# lightBarV2_a.net
KiCad netlist of a schematic drawn in EAGLE
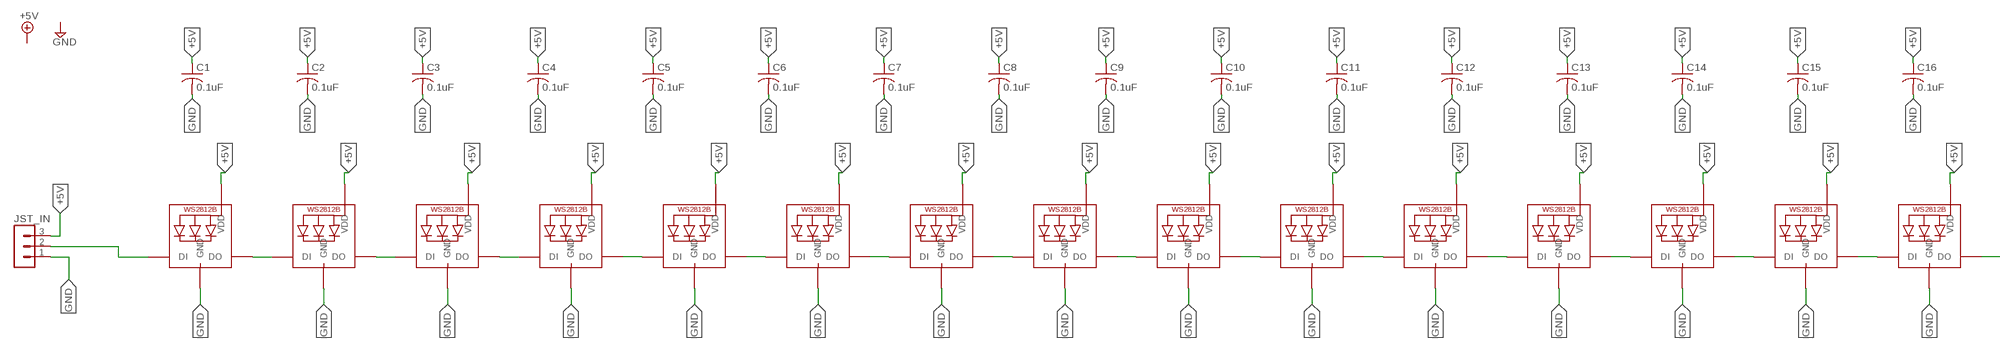
[diagram p0: schematic, sheet 1, part 1 of 2]
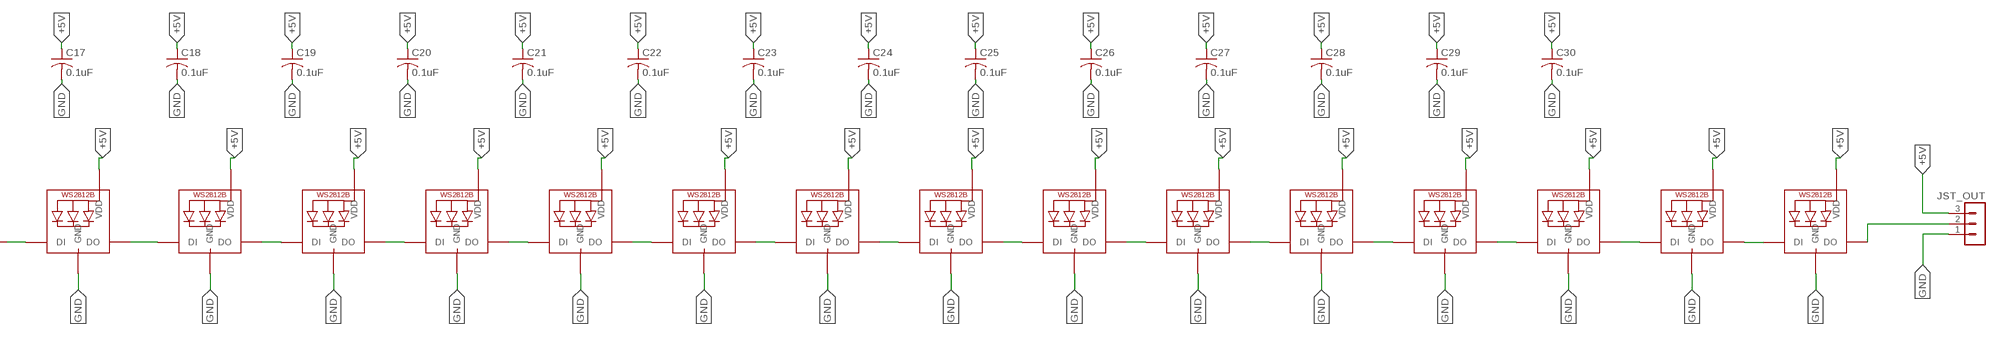
[diagram p1: schematic, sheet 1, part 2 of 2]

(export (version "E")
  (design (tool "Eeschema 10.0.6"))
  (components
    (comp (ref "C1")
      (value "0.1uF")
      (footprint "eagle-import:C0805K")
      (libsource (lib "eagle-import") (part "C-USC0805K"))
    )
    (comp (ref "C2")
      (value "0.1uF")
      (footprint "eagle-import:C0805K")
      (libsource (lib "eagle-import") (part "C-USC0805K"))
    )
    (comp (ref "C3")
      (value "0.1uF")
      (footprint "eagle-import:C0805K")
      (libsource (lib "eagle-import") (part "C-USC0805K"))
    )
    (comp (ref "C4")
      (value "0.1uF")
      (footprint "eagle-import:C0805K")
      (libsource (lib "eagle-import") (part "C-USC0805K"))
    )
    (comp (ref "C5")
      (value "0.1uF")
      (footprint "eagle-import:C0805K")
      (libsource (lib "eagle-import") (part "C-USC0805K"))
    )
    (comp (ref "C6")
      (value "0.1uF")
      (footprint "eagle-import:C0805K")
      (libsource (lib "eagle-import") (part "C-USC0805K"))
    )
    (comp (ref "C7")
      (value "0.1uF")
      (footprint "eagle-import:C0805K")
      (libsource (lib "eagle-import") (part "C-USC0805K"))
    )
    (comp (ref "C8")
      (value "0.1uF")
      (footprint "eagle-import:C0805K")
      (libsource (lib "eagle-import") (part "C-USC0805K"))
    )
    (comp (ref "C9")
      (value "0.1uF")
      (footprint "eagle-import:C0805K")
      (libsource (lib "eagle-import") (part "C-USC0805K"))
    )
    (comp (ref "C10")
      (value "0.1uF")
      (footprint "eagle-import:C0805K")
      (libsource (lib "eagle-import") (part "C-USC0805K"))
    )
    (comp (ref "C11")
      (value "0.1uF")
      (footprint "eagle-import:C0805K")
      (libsource (lib "eagle-import") (part "C-USC0805K"))
    )
    (comp (ref "C12")
      (value "0.1uF")
      (footprint "eagle-import:C0805K")
      (libsource (lib "eagle-import") (part "C-USC0805K"))
    )
    (comp (ref "C13")
      (value "0.1uF")
      (footprint "eagle-import:C0805K")
      (libsource (lib "eagle-import") (part "C-USC0805K"))
    )
    (comp (ref "C14")
      (value "0.1uF")
      (footprint "eagle-import:C0805K")
      (libsource (lib "eagle-import") (part "C-USC0805K"))
    )
    (comp (ref "C15")
      (value "0.1uF")
      (footprint "eagle-import:C0805K")
      (libsource (lib "eagle-import") (part "C-USC0805K"))
    )
    (comp (ref "C16")
      (value "0.1uF")
      (footprint "eagle-import:C0805K")
      (libsource (lib "eagle-import") (part "C-USC0805K"))
    )
    (comp (ref "C17")
      (value "0.1uF")
      (footprint "eagle-import:C0805K")
      (libsource (lib "eagle-import") (part "C-USC0805K"))
    )
    (comp (ref "C18")
      (value "0.1uF")
      (footprint "eagle-import:C0805K")
      (libsource (lib "eagle-import") (part "C-USC0805K"))
    )
    (comp (ref "C19")
      (value "0.1uF")
      (footprint "eagle-import:C0805K")
      (libsource (lib "eagle-import") (part "C-USC0805K"))
    )
    (comp (ref "C20")
      (value "0.1uF")
      (footprint "eagle-import:C0805K")
      (libsource (lib "eagle-import") (part "C-USC0805K"))
    )
    (comp (ref "C21")
      (value "0.1uF")
      (footprint "eagle-import:C0805K")
      (libsource (lib "eagle-import") (part "C-USC0805K"))
    )
    (comp (ref "C22")
      (value "0.1uF")
      (footprint "eagle-import:C0805K")
      (libsource (lib "eagle-import") (part "C-USC0805K"))
    )
    (comp (ref "C23")
      (value "0.1uF")
      (footprint "eagle-import:C0805K")
      (libsource (lib "eagle-import") (part "C-USC0805K"))
    )
    (comp (ref "C24")
      (value "0.1uF")
      (footprint "eagle-import:C0805K")
      (libsource (lib "eagle-import") (part "C-USC0805K"))
    )
    (comp (ref "C25")
      (value "0.1uF")
      (footprint "eagle-import:C0805K")
      (libsource (lib "eagle-import") (part "C-USC0805K"))
    )
    (comp (ref "C26")
      (value "0.1uF")
      (footprint "eagle-import:C0805K")
      (libsource (lib "eagle-import") (part "C-USC0805K"))
    )
    (comp (ref "C27")
      (value "0.1uF")
      (footprint "eagle-import:C0805K")
      (libsource (lib "eagle-import") (part "C-USC0805K"))
    )
    (comp (ref "C28")
      (value "0.1uF")
      (footprint "eagle-import:C0805K")
      (libsource (lib "eagle-import") (part "C-USC0805K"))
    )
    (comp (ref "C29")
      (value "0.1uF")
      (footprint "eagle-import:C0805K")
      (libsource (lib "eagle-import") (part "C-USC0805K"))
    )
    (comp (ref "C30")
      (value "0.1uF")
      (footprint "eagle-import:C0805K")
      (libsource (lib "eagle-import") (part "C-USC0805K"))
    )
    (comp (ref "JST_IN")
      (value "B3B-XH-2")
      (footprint "eagle-import:B3B-XH-A")
      (libsource (lib "eagle-import") (part "B3B-XH-2"))
    )
    (comp (ref "JST_OUT")
      (value "B3B-XH-2")
      (footprint "eagle-import:B3B-XH-A")
      (libsource (lib "eagle-import") (part "B3B-XH-2"))
    )
    (comp (ref "LED1")
      (value "WS2812B5050")
      (footprint "eagle-import:WS2812B")
      (libsource (lib "eagle-import") (part "WS2812B5050"))
    )
    (comp (ref "LED2")
      (value "WS2812B5050")
      (footprint "eagle-import:WS2812B")
      (libsource (lib "eagle-import") (part "WS2812B5050"))
    )
    (comp (ref "LED3")
      (value "WS2812B5050")
      (footprint "eagle-import:WS2812B")
      (libsource (lib "eagle-import") (part "WS2812B5050"))
    )
    (comp (ref "LED4")
      (value "WS2812B5050")
      (footprint "eagle-import:WS2812B")
      (libsource (lib "eagle-import") (part "WS2812B5050"))
    )
    (comp (ref "LED5")
      (value "WS2812B5050")
      (footprint "eagle-import:WS2812B")
      (libsource (lib "eagle-import") (part "WS2812B5050"))
    )
    (comp (ref "LED6")
      (value "WS2812B5050")
      (footprint "eagle-import:WS2812B")
      (libsource (lib "eagle-import") (part "WS2812B5050"))
    )
    (comp (ref "LED7")
      (value "WS2812B5050")
      (footprint "eagle-import:WS2812B")
      (libsource (lib "eagle-import") (part "WS2812B5050"))
    )
    (comp (ref "LED8")
      (value "WS2812B5050")
      (footprint "eagle-import:WS2812B")
      (libsource (lib "eagle-import") (part "WS2812B5050"))
    )
    (comp (ref "LED9")
      (value "WS2812B5050")
      (footprint "eagle-import:WS2812B")
      (libsource (lib "eagle-import") (part "WS2812B5050"))
    )
    (comp (ref "LED10")
      (value "WS2812B5050")
      (footprint "eagle-import:WS2812B")
      (libsource (lib "eagle-import") (part "WS2812B5050"))
    )
    (comp (ref "LED11")
      (value "WS2812B5050")
      (footprint "eagle-import:WS2812B")
      (libsource (lib "eagle-import") (part "WS2812B5050"))
    )
    (comp (ref "LED12")
      (value "WS2812B5050")
      (footprint "eagle-import:WS2812B")
      (libsource (lib "eagle-import") (part "WS2812B5050"))
    )
    (comp (ref "LED13")
      (value "WS2812B5050")
      (footprint "eagle-import:WS2812B")
      (libsource (lib "eagle-import") (part "WS2812B5050"))
    )
    (comp (ref "LED14")
      (value "WS2812B5050")
      (footprint "eagle-import:WS2812B")
      (libsource (lib "eagle-import") (part "WS2812B5050"))
    )
    (comp (ref "LED15")
      (value "WS2812B5050")
      (footprint "eagle-import:WS2812B")
      (libsource (lib "eagle-import") (part "WS2812B5050"))
    )
    (comp (ref "LED16")
      (value "WS2812B5050")
      (footprint "eagle-import:WS2812B")
      (libsource (lib "eagle-import") (part "WS2812B5050"))
    )
    (comp (ref "LED17")
      (value "WS2812B5050")
      (footprint "eagle-import:WS2812B")
      (libsource (lib "eagle-import") (part "WS2812B5050"))
    )
    (comp (ref "LED18")
      (value "WS2812B5050")
      (footprint "eagle-import:WS2812B")
      (libsource (lib "eagle-import") (part "WS2812B5050"))
    )
    (comp (ref "LED19")
      (value "WS2812B5050")
      (footprint "eagle-import:WS2812B")
      (libsource (lib "eagle-import") (part "WS2812B5050"))
    )
    (comp (ref "LED20")
      (value "WS2812B5050")
      (footprint "eagle-import:WS2812B")
      (libsource (lib "eagle-import") (part "WS2812B5050"))
    )
    (comp (ref "LED21")
      (value "WS2812B5050")
      (footprint "eagle-import:WS2812B")
      (libsource (lib "eagle-import") (part "WS2812B5050"))
    )
    (comp (ref "LED22")
      (value "WS2812B5050")
      (footprint "eagle-import:WS2812B")
      (libsource (lib "eagle-import") (part "WS2812B5050"))
    )
    (comp (ref "LED23")
      (value "WS2812B5050")
      (footprint "eagle-import:WS2812B")
      (libsource (lib "eagle-import") (part "WS2812B5050"))
    )
    (comp (ref "LED24")
      (value "WS2812B5050")
      (footprint "eagle-import:WS2812B")
      (libsource (lib "eagle-import") (part "WS2812B5050"))
    )
    (comp (ref "LED25")
      (value "WS2812B5050")
      (footprint "eagle-import:WS2812B")
      (libsource (lib "eagle-import") (part "WS2812B5050"))
    )
    (comp (ref "LED26")
      (value "WS2812B5050")
      (footprint "eagle-import:WS2812B")
      (libsource (lib "eagle-import") (part "WS2812B5050"))
    )
    (comp (ref "LED27")
      (value "WS2812B5050")
      (footprint "eagle-import:WS2812B")
      (libsource (lib "eagle-import") (part "WS2812B5050"))
    )
    (comp (ref "LED28")
      (value "WS2812B5050")
      (footprint "eagle-import:WS2812B")
      (libsource (lib "eagle-import") (part "WS2812B5050"))
    )
    (comp (ref "LED29")
      (value "WS2812B5050")
      (footprint "eagle-import:WS2812B")
      (libsource (lib "eagle-import") (part "WS2812B5050"))
    )
    (comp (ref "LED30")
      (value "WS2812B5050")
      (footprint "eagle-import:WS2812B")
      (libsource (lib "eagle-import") (part "WS2812B5050"))
    )
  )
  (nets
    (net (code "1") (name "+5V") (class "Default")
      (node (ref "C1") (pin "1") (pinfunction "1_1") (pintype "passive"))
      (node (ref "C10") (pin "1") (pinfunction "1_1") (pintype "passive"))
      (node (ref "C11") (pin "1") (pinfunction "1_1") (pintype "passive"))
      (node (ref "C12") (pin "1") (pinfunction "1_1") (pintype "passive"))
      (node (ref "C13") (pin "1") (pinfunction "1_1") (pintype "passive"))
      (node (ref "C14") (pin "1") (pinfunction "1_1") (pintype "passive"))
      (node (ref "C15") (pin "1") (pinfunction "1_1") (pintype "passive"))
      (node (ref "C16") (pin "1") (pinfunction "1_1") (pintype "passive"))
      (node (ref "C17") (pin "1") (pinfunction "1_1") (pintype "passive"))
      (node (ref "C18") (pin "1") (pinfunction "1_1") (pintype "passive"))
      (node (ref "C19") (pin "1") (pinfunction "1_1") (pintype "passive"))
      (node (ref "C2") (pin "1") (pinfunction "1_1") (pintype "passive"))
      (node (ref "C20") (pin "1") (pinfunction "1_1") (pintype "passive"))
      (node (ref "C21") (pin "1") (pinfunction "1_1") (pintype "passive"))
      (node (ref "C22") (pin "1") (pinfunction "1_1") (pintype "passive"))
      (node (ref "C23") (pin "1") (pinfunction "1_1") (pintype "passive"))
      (node (ref "C24") (pin "1") (pinfunction "1_1") (pintype "passive"))
      (node (ref "C25") (pin "1") (pinfunction "1_1") (pintype "passive"))
      (node (ref "C26") (pin "1") (pinfunction "1_1") (pintype "passive"))
      (node (ref "C27") (pin "1") (pinfunction "1_1") (pintype "passive"))
      (node (ref "C28") (pin "1") (pinfunction "1_1") (pintype "passive"))
      (node (ref "C29") (pin "1") (pinfunction "1_1") (pintype "passive"))
      (node (ref "C3") (pin "1") (pinfunction "1_1") (pintype "passive"))
      (node (ref "C30") (pin "1") (pinfunction "1_1") (pintype "passive"))
      (node (ref "C4") (pin "1") (pinfunction "1_1") (pintype "passive"))
      (node (ref "C5") (pin "1") (pinfunction "1_1") (pintype "passive"))
      (node (ref "C6") (pin "1") (pinfunction "1_1") (pintype "passive"))
      (node (ref "C7") (pin "1") (pinfunction "1_1") (pintype "passive"))
      (node (ref "C8") (pin "1") (pinfunction "1_1") (pintype "passive"))
      (node (ref "C9") (pin "1") (pinfunction "1_1") (pintype "passive"))
      (node (ref "JST_IN") (pin "3") (pinfunction "3_3") (pintype "passive"))
      (node (ref "JST_OUT") (pin "3") (pinfunction "3_3") (pintype "passive"))
      (node (ref "LED1") (pin "1-VDD") (pinfunction "VDD_1-VDD") (pintype "power_in"))
      (node (ref "LED10") (pin "1-VDD") (pinfunction "VDD_1-VDD") (pintype "power_in"))
      (node (ref "LED11") (pin "1-VDD") (pinfunction "VDD_1-VDD") (pintype "power_in"))
      (node (ref "LED12") (pin "1-VDD") (pinfunction "VDD_1-VDD") (pintype "power_in"))
      (node (ref "LED13") (pin "1-VDD") (pinfunction "VDD_1-VDD") (pintype "power_in"))
      (node (ref "LED14") (pin "1-VDD") (pinfunction "VDD_1-VDD") (pintype "power_in"))
      (node (ref "LED15") (pin "1-VDD") (pinfunction "VDD_1-VDD") (pintype "power_in"))
      (node (ref "LED16") (pin "1-VDD") (pinfunction "VDD_1-VDD") (pintype "power_in"))
      (node (ref "LED17") (pin "1-VDD") (pinfunction "VDD_1-VDD") (pintype "power_in"))
      (node (ref "LED18") (pin "1-VDD") (pinfunction "VDD_1-VDD") (pintype "power_in"))
      (node (ref "LED19") (pin "1-VDD") (pinfunction "VDD_1-VDD") (pintype "power_in"))
      (node (ref "LED2") (pin "1-VDD") (pinfunction "VDD_1-VDD") (pintype "power_in"))
      (node (ref "LED20") (pin "1-VDD") (pinfunction "VDD_1-VDD") (pintype "power_in"))
      (node (ref "LED21") (pin "1-VDD") (pinfunction "VDD_1-VDD") (pintype "power_in"))
      (node (ref "LED22") (pin "1-VDD") (pinfunction "VDD_1-VDD") (pintype "power_in"))
      (node (ref "LED23") (pin "1-VDD") (pinfunction "VDD_1-VDD") (pintype "power_in"))
      (node (ref "LED24") (pin "1-VDD") (pinfunction "VDD_1-VDD") (pintype "power_in"))
      (node (ref "LED25") (pin "1-VDD") (pinfunction "VDD_1-VDD") (pintype "power_in"))
      (node (ref "LED26") (pin "1-VDD") (pinfunction "VDD_1-VDD") (pintype "power_in"))
      (node (ref "LED27") (pin "1-VDD") (pinfunction "VDD_1-VDD") (pintype "power_in"))
      (node (ref "LED28") (pin "1-VDD") (pinfunction "VDD_1-VDD") (pintype "power_in"))
      (node (ref "LED29") (pin "1-VDD") (pinfunction "VDD_1-VDD") (pintype "power_in"))
      (node (ref "LED3") (pin "1-VDD") (pinfunction "VDD_1-VDD") (pintype "power_in"))
      (node (ref "LED30") (pin "1-VDD") (pinfunction "VDD_1-VDD") (pintype "power_in"))
      (node (ref "LED4") (pin "1-VDD") (pinfunction "VDD_1-VDD") (pintype "power_in"))
      (node (ref "LED5") (pin "1-VDD") (pinfunction "VDD_1-VDD") (pintype "power_in"))
      (node (ref "LED6") (pin "1-VDD") (pinfunction "VDD_1-VDD") (pintype "power_in"))
      (node (ref "LED7") (pin "1-VDD") (pinfunction "VDD_1-VDD") (pintype "power_in"))
      (node (ref "LED8") (pin "1-VDD") (pinfunction "VDD_1-VDD") (pintype "power_in"))
      (node (ref "LED9") (pin "1-VDD") (pinfunction "VDD_1-VDD") (pintype "power_in"))
    )
    (net (code "2") (name "GND") (class "Default")
      (node (ref "C1") (pin "2") (pinfunction "2_2") (pintype "passive"))
      (node (ref "C10") (pin "2") (pinfunction "2_2") (pintype "passive"))
      (node (ref "C11") (pin "2") (pinfunction "2_2") (pintype "passive"))
      (node (ref "C12") (pin "2") (pinfunction "2_2") (pintype "passive"))
      (node (ref "C13") (pin "2") (pinfunction "2_2") (pintype "passive"))
      (node (ref "C14") (pin "2") (pinfunction "2_2") (pintype "passive"))
      (node (ref "C15") (pin "2") (pinfunction "2_2") (pintype "passive"))
      (node (ref "C16") (pin "2") (pinfunction "2_2") (pintype "passive"))
      (node (ref "C17") (pin "2") (pinfunction "2_2") (pintype "passive"))
      (node (ref "C18") (pin "2") (pinfunction "2_2") (pintype "passive"))
      (node (ref "C19") (pin "2") (pinfunction "2_2") (pintype "passive"))
      (node (ref "C2") (pin "2") (pinfunction "2_2") (pintype "passive"))
      (node (ref "C20") (pin "2") (pinfunction "2_2") (pintype "passive"))
      (node (ref "C21") (pin "2") (pinfunction "2_2") (pintype "passive"))
      (node (ref "C22") (pin "2") (pinfunction "2_2") (pintype "passive"))
      (node (ref "C23") (pin "2") (pinfunction "2_2") (pintype "passive"))
      (node (ref "C24") (pin "2") (pinfunction "2_2") (pintype "passive"))
      (node (ref "C25") (pin "2") (pinfunction "2_2") (pintype "passive"))
      (node (ref "C26") (pin "2") (pinfunction "2_2") (pintype "passive"))
      (node (ref "C27") (pin "2") (pinfunction "2_2") (pintype "passive"))
      (node (ref "C28") (pin "2") (pinfunction "2_2") (pintype "passive"))
      (node (ref "C29") (pin "2") (pinfunction "2_2") (pintype "passive"))
      (node (ref "C3") (pin "2") (pinfunction "2_2") (pintype "passive"))
      (node (ref "C30") (pin "2") (pinfunction "2_2") (pintype "passive"))
      (node (ref "C4") (pin "2") (pinfunction "2_2") (pintype "passive"))
      (node (ref "C5") (pin "2") (pinfunction "2_2") (pintype "passive"))
      (node (ref "C6") (pin "2") (pinfunction "2_2") (pintype "passive"))
      (node (ref "C7") (pin "2") (pinfunction "2_2") (pintype "passive"))
      (node (ref "C8") (pin "2") (pinfunction "2_2") (pintype "passive"))
      (node (ref "C9") (pin "2") (pinfunction "2_2") (pintype "passive"))
      (node (ref "JST_IN") (pin "1") (pinfunction "1_1") (pintype "passive"))
      (node (ref "JST_OUT") (pin "1") (pinfunction "1_1") (pintype "passive"))
      (node (ref "LED1") (pin "3-GND") (pinfunction "GND_3-GND") (pintype "power_in"))
      (node (ref "LED10") (pin "3-GND") (pinfunction "GND_3-GND") (pintype "power_in"))
      (node (ref "LED11") (pin "3-GND") (pinfunction "GND_3-GND") (pintype "power_in"))
      (node (ref "LED12") (pin "3-GND") (pinfunction "GND_3-GND") (pintype "power_in"))
      (node (ref "LED13") (pin "3-GND") (pinfunction "GND_3-GND") (pintype "power_in"))
      (node (ref "LED14") (pin "3-GND") (pinfunction "GND_3-GND") (pintype "power_in"))
      (node (ref "LED15") (pin "3-GND") (pinfunction "GND_3-GND") (pintype "power_in"))
      (node (ref "LED16") (pin "3-GND") (pinfunction "GND_3-GND") (pintype "power_in"))
      (node (ref "LED17") (pin "3-GND") (pinfunction "GND_3-GND") (pintype "power_in"))
      (node (ref "LED18") (pin "3-GND") (pinfunction "GND_3-GND") (pintype "power_in"))
      (node (ref "LED19") (pin "3-GND") (pinfunction "GND_3-GND") (pintype "power_in"))
      (node (ref "LED2") (pin "3-GND") (pinfunction "GND_3-GND") (pintype "power_in"))
      (node (ref "LED20") (pin "3-GND") (pinfunction "GND_3-GND") (pintype "power_in"))
      (node (ref "LED21") (pin "3-GND") (pinfunction "GND_3-GND") (pintype "power_in"))
      (node (ref "LED22") (pin "3-GND") (pinfunction "GND_3-GND") (pintype "power_in"))
      (node (ref "LED23") (pin "3-GND") (pinfunction "GND_3-GND") (pintype "power_in"))
      (node (ref "LED24") (pin "3-GND") (pinfunction "GND_3-GND") (pintype "power_in"))
      (node (ref "LED25") (pin "3-GND") (pinfunction "GND_3-GND") (pintype "power_in"))
      (node (ref "LED26") (pin "3-GND") (pinfunction "GND_3-GND") (pintype "power_in"))
      (node (ref "LED27") (pin "3-GND") (pinfunction "GND_3-GND") (pintype "power_in"))
      (node (ref "LED28") (pin "3-GND") (pinfunction "GND_3-GND") (pintype "power_in"))
      (node (ref "LED29") (pin "3-GND") (pinfunction "GND_3-GND") (pintype "power_in"))
      (node (ref "LED3") (pin "3-GND") (pinfunction "GND_3-GND") (pintype "power_in"))
      (node (ref "LED30") (pin "3-GND") (pinfunction "GND_3-GND") (pintype "power_in"))
      (node (ref "LED4") (pin "3-GND") (pinfunction "GND_3-GND") (pintype "power_in"))
      (node (ref "LED5") (pin "3-GND") (pinfunction "GND_3-GND") (pintype "power_in"))
      (node (ref "LED6") (pin "3-GND") (pinfunction "GND_3-GND") (pintype "power_in"))
      (node (ref "LED7") (pin "3-GND") (pinfunction "GND_3-GND") (pintype "power_in"))
      (node (ref "LED8") (pin "3-GND") (pinfunction "GND_3-GND") (pintype "power_in"))
      (node (ref "LED9") (pin "3-GND") (pinfunction "GND_3-GND") (pintype "power_in"))
    )
    (net (code "3") (name "Net-(LED1-DI)") (class "Default")
      (node (ref "JST_IN") (pin "2") (pinfunction "2_2") (pintype "passive"))
      (node (ref "LED1") (pin "4-DIN") (pinfunction "DI_4-DIN") (pintype "input"))
    )
    (net (code "4") (name "Net-(LED1-DO)") (class "Default")
      (node (ref "LED1") (pin "2-DOUT") (pinfunction "DO_2-DOUT") (pintype "output"))
      (node (ref "LED2") (pin "4-DIN") (pinfunction "DI_4-DIN") (pintype "input"))
    )
    (net (code "5") (name "Net-(LED2-DO)") (class "Default")
      (node (ref "LED2") (pin "2-DOUT") (pinfunction "DO_2-DOUT") (pintype "output"))
      (node (ref "LED3") (pin "4-DIN") (pinfunction "DI_4-DIN") (pintype "input"))
    )
    (net (code "6") (name "Net-(LED3-DO)") (class "Default")
      (node (ref "LED3") (pin "2-DOUT") (pinfunction "DO_2-DOUT") (pintype "output"))
      (node (ref "LED4") (pin "4-DIN") (pinfunction "DI_4-DIN") (pintype "input"))
    )
    (net (code "7") (name "Net-(LED4-DO)") (class "Default")
      (node (ref "LED4") (pin "2-DOUT") (pinfunction "DO_2-DOUT") (pintype "output"))
      (node (ref "LED5") (pin "4-DIN") (pinfunction "DI_4-DIN") (pintype "input"))
    )
    (net (code "8") (name "Net-(LED5-DO)") (class "Default")
      (node (ref "LED5") (pin "2-DOUT") (pinfunction "DO_2-DOUT") (pintype "output"))
      (node (ref "LED6") (pin "4-DIN") (pinfunction "DI_4-DIN") (pintype "input"))
    )
    (net (code "9") (name "Net-(LED6-DO)") (class "Default")
      (node (ref "LED6") (pin "2-DOUT") (pinfunction "DO_2-DOUT") (pintype "output"))
      (node (ref "LED7") (pin "4-DIN") (pinfunction "DI_4-DIN") (pintype "input"))
    )
    (net (code "10") (name "Net-(LED7-DO)") (class "Default")
      (node (ref "LED7") (pin "2-DOUT") (pinfunction "DO_2-DOUT") (pintype "output"))
      (node (ref "LED8") (pin "4-DIN") (pinfunction "DI_4-DIN") (pintype "input"))
    )
    (net (code "11") (name "Net-(LED8-DO)") (class "Default")
      (node (ref "LED8") (pin "2-DOUT") (pinfunction "DO_2-DOUT") (pintype "output"))
      (node (ref "LED9") (pin "4-DIN") (pinfunction "DI_4-DIN") (pintype "input"))
    )
    (net (code "12") (name "Net-(LED10-DI)") (class "Default")
      (node (ref "LED10") (pin "4-DIN") (pinfunction "DI_4-DIN") (pintype "input"))
      (node (ref "LED9") (pin "2-DOUT") (pinfunction "DO_2-DOUT") (pintype "output"))
    )
    (net (code "13") (name "Net-(LED10-DO)") (class "Default")
      (node (ref "LED10") (pin "2-DOUT") (pinfunction "DO_2-DOUT") (pintype "output"))
      (node (ref "LED11") (pin "4-DIN") (pinfunction "DI_4-DIN") (pintype "input"))
    )
    (net (code "14") (name "Net-(LED11-DO)") (class "Default")
      (node (ref "LED11") (pin "2-DOUT") (pinfunction "DO_2-DOUT") (pintype "output"))
      (node (ref "LED12") (pin "4-DIN") (pinfunction "DI_4-DIN") (pintype "input"))
    )
    (net (code "15") (name "Net-(LED12-DO)") (class "Default")
      (node (ref "LED12") (pin "2-DOUT") (pinfunction "DO_2-DOUT") (pintype "output"))
      (node (ref "LED13") (pin "4-DIN") (pinfunction "DI_4-DIN") (pintype "input"))
    )
    (net (code "16") (name "Net-(LED13-DO)") (class "Default")
      (node (ref "LED13") (pin "2-DOUT") (pinfunction "DO_2-DOUT") (pintype "output"))
      (node (ref "LED14") (pin "4-DIN") (pinfunction "DI_4-DIN") (pintype "input"))
    )
    (net (code "17") (name "Net-(LED14-DO)") (class "Default")
      (node (ref "LED14") (pin "2-DOUT") (pinfunction "DO_2-DOUT") (pintype "output"))
      (node (ref "LED15") (pin "4-DIN") (pinfunction "DI_4-DIN") (pintype "input"))
    )
    (net (code "18") (name "Net-(LED15-DO)") (class "Default")
      (node (ref "LED15") (pin "2-DOUT") (pinfunction "DO_2-DOUT") (pintype "output"))
      (node (ref "LED16") (pin "4-DIN") (pinfunction "DI_4-DIN") (pintype "input"))
    )
    (net (code "19") (name "Net-(LED16-DO)") (class "Default")
      (node (ref "LED16") (pin "2-DOUT") (pinfunction "DO_2-DOUT") (pintype "output"))
      (node (ref "LED17") (pin "4-DIN") (pinfunction "DI_4-DIN") (pintype "input"))
    )
    (net (code "20") (name "Net-(LED17-DO)") (class "Default")
      (node (ref "LED17") (pin "2-DOUT") (pinfunction "DO_2-DOUT") (pintype "output"))
      (node (ref "LED18") (pin "4-DIN") (pinfunction "DI_4-DIN") (pintype "input"))
    )
    (net (code "21") (name "Net-(LED18-DO)") (class "Default")
      (node (ref "LED18") (pin "2-DOUT") (pinfunction "DO_2-DOUT") (pintype "output"))
      (node (ref "LED19") (pin "4-DIN") (pinfunction "DI_4-DIN") (pintype "input"))
    )
    (net (code "22") (name "Net-(LED19-DO)") (class "Default")
      (node (ref "LED19") (pin "2-DOUT") (pinfunction "DO_2-DOUT") (pintype "output"))
      (node (ref "LED20") (pin "4-DIN") (pinfunction "DI_4-DIN") (pintype "input"))
    )
    (net (code "23") (name "Net-(LED20-DO)") (class "Default")
      (node (ref "LED20") (pin "2-DOUT") (pinfunction "DO_2-DOUT") (pintype "output"))
      (node (ref "LED21") (pin "4-DIN") (pinfunction "DI_4-DIN") (pintype "input"))
    )
    (net (code "24") (name "Net-(LED21-DO)") (class "Default")
      (node (ref "LED21") (pin "2-DOUT") (pinfunction "DO_2-DOUT") (pintype "output"))
      (node (ref "LED22") (pin "4-DIN") (pinfunction "DI_4-DIN") (pintype "input"))
    )
    (net (code "25") (name "Net-(LED22-DO)") (class "Default")
      (node (ref "LED22") (pin "2-DOUT") (pinfunction "DO_2-DOUT") (pintype "output"))
      (node (ref "LED23") (pin "4-DIN") (pinfunction "DI_4-DIN") (pintype "input"))
    )
    (net (code "26") (name "Net-(LED23-DO)") (class "Default")
      (node (ref "LED23") (pin "2-DOUT") (pinfunction "DO_2-DOUT") (pintype "output"))
      (node (ref "LED24") (pin "4-DIN") (pinfunction "DI_4-DIN") (pintype "input"))
    )
    (net (code "27") (name "Net-(LED24-DO)") (class "Default")
      (node (ref "LED24") (pin "2-DOUT") (pinfunction "DO_2-DOUT") (pintype "output"))
      (node (ref "LED25") (pin "4-DIN") (pinfunction "DI_4-DIN") (pintype "input"))
    )
    (net (code "28") (name "Net-(LED25-DO)") (class "Default")
      (node (ref "LED25") (pin "2-DOUT") (pinfunction "DO_2-DOUT") (pintype "output"))
      (node (ref "LED26") (pin "4-DIN") (pinfunction "DI_4-DIN") (pintype "input"))
    )
    (net (code "29") (name "Net-(LED26-DO)") (class "Default")
      (node (ref "LED26") (pin "2-DOUT") (pinfunction "DO_2-DOUT") (pintype "output"))
      (node (ref "LED27") (pin "4-DIN") (pinfunction "DI_4-DIN") (pintype "input"))
    )
    (net (code "30") (name "Net-(LED27-DO)") (class "Default")
      (node (ref "LED27") (pin "2-DOUT") (pinfunction "DO_2-DOUT") (pintype "output"))
      (node (ref "LED28") (pin "4-DIN") (pinfunction "DI_4-DIN") (pintype "input"))
    )
    (net (code "31") (name "Net-(LED28-DO)") (class "Default")
      (node (ref "LED28") (pin "2-DOUT") (pinfunction "DO_2-DOUT") (pintype "output"))
      (node (ref "LED29") (pin "4-DIN") (pinfunction "DI_4-DIN") (pintype "input"))
    )
    (net (code "32") (name "Net-(LED29-DO)") (class "Default")
      (node (ref "LED29") (pin "2-DOUT") (pinfunction "DO_2-DOUT") (pintype "output"))
      (node (ref "LED30") (pin "4-DIN") (pinfunction "DI_4-DIN") (pintype "input"))
    )
    (net (code "33") (name "Net-(LED30-DO)") (class "Default")
      (node (ref "JST_OUT") (pin "2") (pinfunction "2_2") (pintype "passive"))
      (node (ref "LED30") (pin "2-DOUT") (pinfunction "DO_2-DOUT") (pintype "output"))
    )
  )
)
